# Schematic_Kpad.net
KiCad netlist of a schematic drawn in Altium Designer
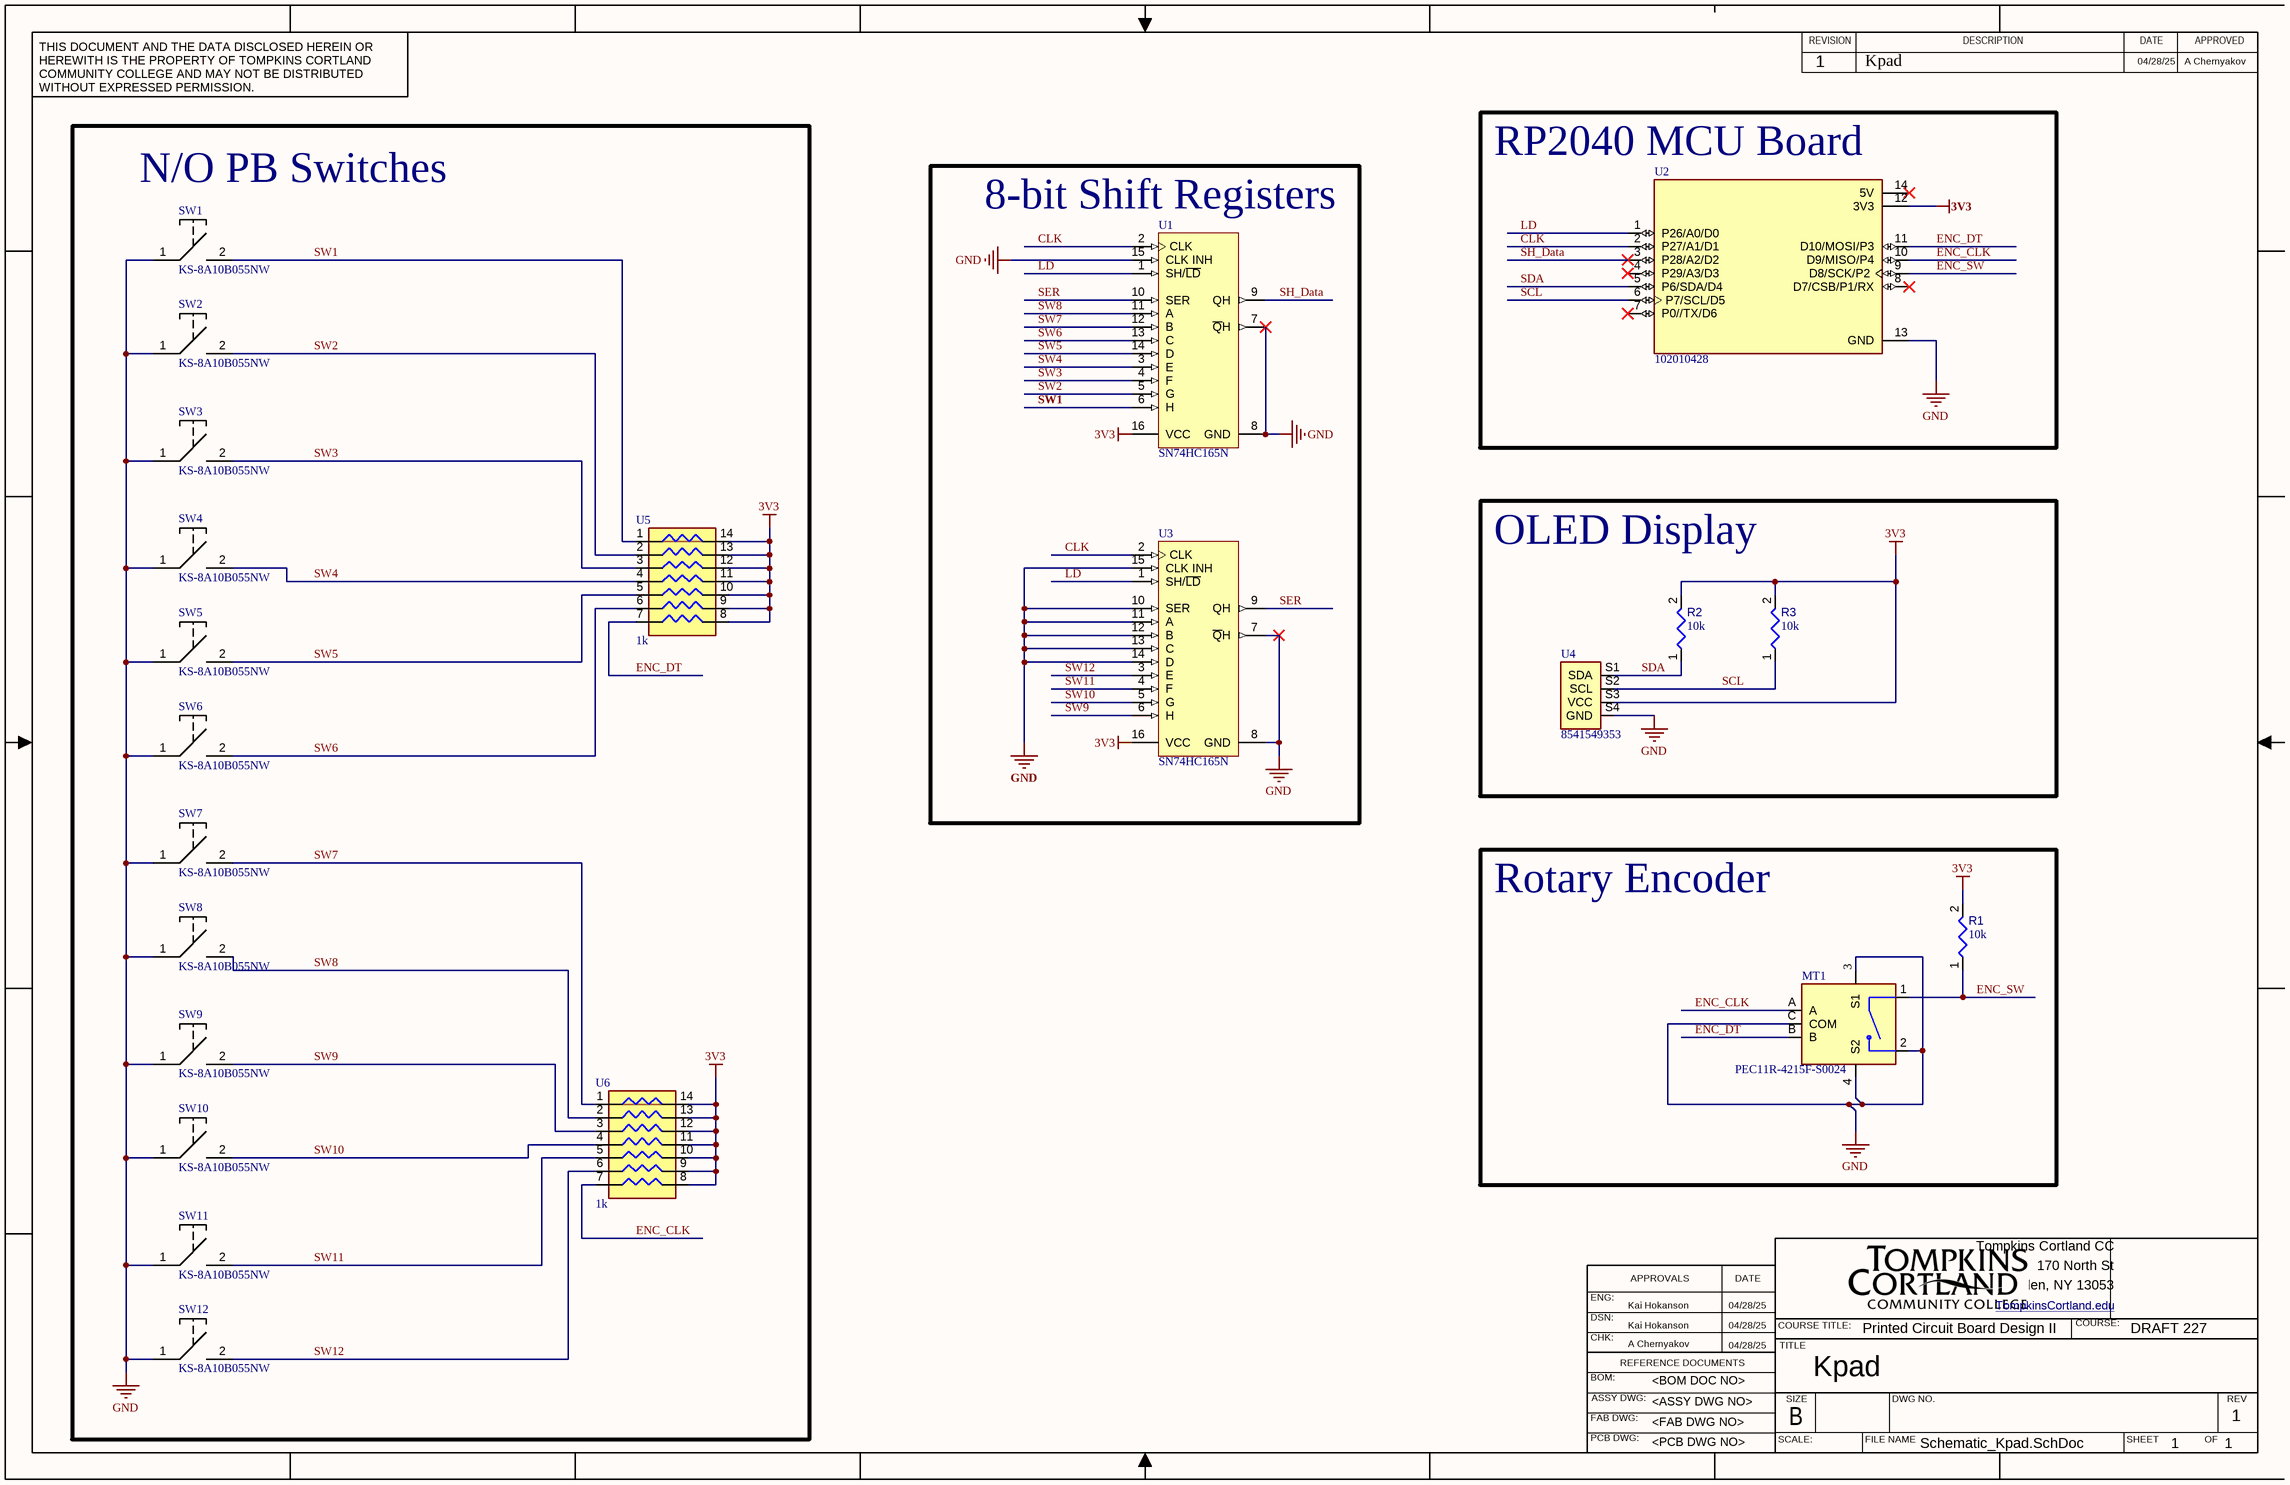
[diagram p0: Schematic_Kpad.SchDoc]

(export (version "E")
  (design (tool "Eeschema 10.0.6"))
  (components
    (comp (ref "MT1")
      (value "PEC11R-4215F-S0024")
      (footprint "FP-PEC11R-4215F-S0024-MFG")
      (description "Incremental Encoder, 12 Mm, Contact Rating 10 Ma - 5 Vdc")
      (libsource (lib "Tompkins Cortland Community College") (part "PEC11R-4215F-S0024"))
    )
    (comp (ref "R1")
      (value "10k")
      (footprint "RESA60-630X240")
      (description "Axial Resistor, 10 KOhm, +/- 1%, 0.25 W, -55 to 155 degC, 2-Pin THD, RoHS, Bulk")
      (fields (field (name "TOLERANCE") "1%") (field (name "POWER") "250mW"))
      (libsource (lib "Tompkins Cortland Community College") (part "RES-2"))
    )
    (comp (ref "R2")
      (value "10k")
      (footprint "RESA60-630X240")
      (description "Axial Resistor, 10 KOhm, +/- 1%, 0.25 W, -55 to 155 degC, 2-Pin THD, RoHS, Bulk")
      (fields (field (name "TOLERANCE") "1%") (field (name "POWER") "250mW"))
      (libsource (lib "Tompkins Cortland Community College") (part "RES-2"))
    )
    (comp (ref "R3")
      (value "10k")
      (footprint "RESA60-630X240")
      (description "Axial Resistor, 10 KOhm, +/- 1%, 0.25 W, -55 to 155 degC, 2-Pin THD, RoHS, Bulk")
      (fields (field (name "TOLERANCE") "1%") (field (name "POWER") "250mW"))
      (libsource (lib "Tompkins Cortland Community College") (part "RES-2"))
    )
    (comp (ref "SW1")
      (value "KS-8A10B055NW")
      (footprint "KS-8A10B055NW-Footprint-1")
      (description "SPST momentary switch 15.40mmx15.40mm")
      (libsource (lib "Tompkins Cortland Community College") (part "KS-8A10B055NW-Symbol-1"))
    )
    (comp (ref "SW2")
      (value "KS-8A10B055NW")
      (footprint "KS-8A10B055NW-Footprint-1")
      (description "SPST momentary switch 15.40mmx15.40mm")
      (libsource (lib "Tompkins Cortland Community College") (part "KS-8A10B055NW-Symbol-1"))
    )
    (comp (ref "SW3")
      (value "KS-8A10B055NW")
      (footprint "KS-8A10B055NW-Footprint-1")
      (description "SPST momentary switch 15.40mmx15.40mm")
      (libsource (lib "Tompkins Cortland Community College") (part "KS-8A10B055NW-Symbol-1"))
    )
    (comp (ref "SW4")
      (value "KS-8A10B055NW")
      (footprint "KS-8A10B055NW-Footprint-1")
      (description "SPST momentary switch 15.40mmx15.40mm")
      (libsource (lib "Tompkins Cortland Community College") (part "KS-8A10B055NW-Symbol-1"))
    )
    (comp (ref "SW5")
      (value "KS-8A10B055NW")
      (footprint "KS-8A10B055NW-Footprint-1")
      (description "SPST momentary switch 15.40mmx15.40mm")
      (libsource (lib "Tompkins Cortland Community College") (part "KS-8A10B055NW-Symbol-1"))
    )
    (comp (ref "SW6")
      (value "KS-8A10B055NW")
      (footprint "KS-8A10B055NW-Footprint-1")
      (description "SPST momentary switch 15.40mmx15.40mm")
      (libsource (lib "Tompkins Cortland Community College") (part "KS-8A10B055NW-Symbol-1"))
    )
    (comp (ref "SW7")
      (value "KS-8A10B055NW")
      (footprint "KS-8A10B055NW-Footprint-1")
      (description "SPST momentary switch 15.40mmx15.40mm")
      (libsource (lib "Tompkins Cortland Community College") (part "KS-8A10B055NW-Symbol-1"))
    )
    (comp (ref "SW8")
      (value "KS-8A10B055NW")
      (footprint "KS-8A10B055NW-Footprint-1")
      (description "SPST momentary switch 15.40mmx15.40mm")
      (libsource (lib "Tompkins Cortland Community College") (part "KS-8A10B055NW-Symbol-1"))
    )
    (comp (ref "SW9")
      (value "KS-8A10B055NW")
      (footprint "KS-8A10B055NW-Footprint-1")
      (description "SPST momentary switch 15.40mmx15.40mm")
      (libsource (lib "Tompkins Cortland Community College") (part "KS-8A10B055NW-Symbol-1"))
    )
    (comp (ref "SW10")
      (value "KS-8A10B055NW")
      (footprint "KS-8A10B055NW-Footprint-1")
      (description "SPST momentary switch 15.40mmx15.40mm")
      (libsource (lib "Tompkins Cortland Community College") (part "KS-8A10B055NW-Symbol-1"))
    )
    (comp (ref "SW11")
      (value "KS-8A10B055NW")
      (footprint "KS-8A10B055NW-Footprint-1")
      (description "SPST momentary switch 15.40mmx15.40mm")
      (libsource (lib "Tompkins Cortland Community College") (part "KS-8A10B055NW-Symbol-1"))
    )
    (comp (ref "SW12")
      (value "KS-8A10B055NW")
      (footprint "KS-8A10B055NW-Footprint-1")
      (description "SPST momentary switch 15.40mmx15.40mm")
      (libsource (lib "Tompkins Cortland Community College") (part "KS-8A10B055NW-Symbol-1"))
    )
    (comp (ref "U1")
      (value "SN74HC165N")
      (footprint "TI-N0016A")
      (libsource (lib "Tompkins Cortland Community College") (part "TI-SNX4XXX165X-16"))
    )
    (comp (ref "U2")
      (value "102010428")
      (footprint "MODULE_102010428")
      (description "RP2040 XIAO RP2040 series ARMÂ® CortexÂ®-M0+ MCU 32-Bit Embedded Evaluation Board")
      (libsource (lib "Tompkins Cortland Community College") (part "102010428"))
    )
    (comp (ref "U3")
      (value "SN74HC165N")
      (footprint "TI-N0016A")
      (libsource (lib "Tompkins Cortland Community College") (part "TI-SNX4XXX165X-16"))
    )
    (comp (ref "U4")
      (value "8541549353")
      (footprint "New footprint 1")
      (description "MakerFocus 2pcs I2C OLED Display Module 0.91 Inch")
      (libsource (lib "Tompkins Cortland Community College") (part "8541549353"))
    )
    (comp (ref "U5")
      (value "1k")
      (footprint "DIP794W45P254L1969H508Q14")
      (description "RES ARRAY 7 RES 1K OHM 14DIP")
      (fields (field (name "TOLERANCE") "2%") (field (name "POWER") "250mW"))
      (libsource (lib "Tompkins Cortland Community College") (part "4114R-1-331LF"))
    )
    (comp (ref "U6")
      (value "1k")
      (footprint "DIP794W45P254L1969H508Q14")
      (description "RES ARRAY 7 RES 1K OHM 14DIP")
      (fields (field (name "TOLERANCE") "2%") (field (name "POWER") "250mW"))
      (libsource (lib "Tompkins Cortland Community College") (part "4114R-1-331LF"))
    )
  )
  (nets
    (net (code "1") (name "/CLK") (class "Default")
      (node (ref "U1") (pin "2") (pinfunction "CLK_2") (pintype "input"))
      (node (ref "U2") (pin "2") (pinfunction "P27/A1/D1_2") (pintype "bidirectional"))
      (node (ref "U3") (pin "2") (pinfunction "CLK_2") (pintype "input"))
    )
    (net (code "2") (name "/ENC_CLK") (class "Default")
      (node (ref "MT1") (pin "A") (pinfunction "A_A") (pintype "passive"))
      (node (ref "U2") (pin "10") (pinfunction "D9/MISO/P4_10") (pintype "bidirectional"))
      (node (ref "U6") (pin "7") (pinfunction "7_7") (pintype "passive"))
    )
    (net (code "3") (name "/ENC_DT") (class "Default")
      (node (ref "MT1") (pin "B") (pinfunction "B_B") (pintype "passive"))
      (node (ref "U2") (pin "11") (pinfunction "D10/MOSI/P3_11") (pintype "bidirectional"))
      (node (ref "U5") (pin "7") (pinfunction "7_7") (pintype "passive"))
    )
    (net (code "4") (name "/ENC_SW") (class "Default")
      (node (ref "MT1") (pin "1") (pinfunction "1_1") (pintype "passive"))
      (node (ref "R1") (pin "1") (pinfunction "1_1") (pintype "passive"))
      (node (ref "U2") (pin "9") (pinfunction "D8/SCK/P2_9") (pintype "bidirectional"))
    )
    (net (code "5") (name "/LD") (class "Default")
      (node (ref "U1") (pin "1") (pinfunction "SH/~{LD}_1") (pintype "input"))
      (node (ref "U2") (pin "1") (pinfunction "P26/A0/D0_1") (pintype "bidirectional"))
      (node (ref "U3") (pin "1") (pinfunction "SH/~{LD}_1") (pintype "input"))
    )
    (net (code "6") (name "/SCL") (class "Default")
      (node (ref "R3") (pin "1") (pinfunction "1_1") (pintype "passive"))
      (node (ref "U2") (pin "6") (pinfunction "P7/SCL/D5_6") (pintype "bidirectional"))
      (node (ref "U4") (pin "S2") (pinfunction "SCL_S2") (pintype "passive"))
    )
    (net (code "7") (name "/SDA") (class "Default")
      (node (ref "R2") (pin "1") (pinfunction "1_1") (pintype "passive"))
      (node (ref "U2") (pin "5") (pinfunction "P6/SDA/D4_5") (pintype "bidirectional"))
      (node (ref "U4") (pin "S1") (pinfunction "SDA_S1") (pintype "passive"))
    )
    (net (code "8") (name "/SER") (class "Default")
      (node (ref "U1") (pin "10") (pinfunction "SER_10") (pintype "input"))
      (node (ref "U3") (pin "9") (pinfunction "QH_9") (pintype "output"))
    )
    (net (code "9") (name "/SH_Data") (class "Default")
      (node (ref "U1") (pin "9") (pinfunction "QH_9") (pintype "output"))
      (node (ref "U2") (pin "3") (pinfunction "P28/A2/D2_3") (pintype "bidirectional"))
    )
    (net (code "10") (name "/SW1") (class "Default")
      (node (ref "SW1") (pin "2") (pinfunction "2_2") (pintype "passive"))
      (node (ref "U1") (pin "6") (pinfunction "H_6") (pintype "input"))
      (node (ref "U5") (pin "1") (pinfunction "1_1") (pintype "passive"))
    )
    (net (code "11") (name "/SW2") (class "Default")
      (node (ref "SW2") (pin "2") (pinfunction "2_2") (pintype "passive"))
      (node (ref "U1") (pin "5") (pinfunction "G_5") (pintype "input"))
      (node (ref "U5") (pin "2") (pinfunction "2_2") (pintype "passive"))
    )
    (net (code "12") (name "/SW3") (class "Default")
      (node (ref "SW3") (pin "2") (pinfunction "2_2") (pintype "passive"))
      (node (ref "U1") (pin "4") (pinfunction "F_4") (pintype "input"))
      (node (ref "U5") (pin "3") (pinfunction "3_3") (pintype "passive"))
    )
    (net (code "13") (name "/SW4") (class "Default")
      (node (ref "SW4") (pin "2") (pinfunction "2_2") (pintype "passive"))
      (node (ref "U1") (pin "3") (pinfunction "E_3") (pintype "input"))
      (node (ref "U5") (pin "4") (pinfunction "4_4") (pintype "passive"))
    )
    (net (code "14") (name "/SW5") (class "Default")
      (node (ref "SW5") (pin "2") (pinfunction "2_2") (pintype "passive"))
      (node (ref "U1") (pin "14") (pinfunction "D_14") (pintype "input"))
      (node (ref "U5") (pin "5") (pinfunction "5_5") (pintype "passive"))
    )
    (net (code "15") (name "/SW6") (class "Default")
      (node (ref "SW6") (pin "2") (pinfunction "2_2") (pintype "passive"))
      (node (ref "U1") (pin "13") (pinfunction "C_13") (pintype "input"))
      (node (ref "U5") (pin "6") (pinfunction "6_6") (pintype "passive"))
    )
    (net (code "16") (name "/SW7") (class "Default")
      (node (ref "SW7") (pin "2") (pinfunction "2_2") (pintype "passive"))
      (node (ref "U1") (pin "12") (pinfunction "B_12") (pintype "input"))
      (node (ref "U6") (pin "1") (pinfunction "1_1") (pintype "passive"))
    )
    (net (code "17") (name "/SW8") (class "Default")
      (node (ref "SW8") (pin "2") (pinfunction "2_2") (pintype "passive"))
      (node (ref "U1") (pin "11") (pinfunction "A_11") (pintype "input"))
      (node (ref "U6") (pin "2") (pinfunction "2_2") (pintype "passive"))
    )
    (net (code "18") (name "/SW9") (class "Default")
      (node (ref "SW9") (pin "2") (pinfunction "2_2") (pintype "passive"))
      (node (ref "U3") (pin "6") (pinfunction "H_6") (pintype "input"))
      (node (ref "U6") (pin "3") (pinfunction "3_3") (pintype "passive"))
    )
    (net (code "19") (name "/SW10") (class "Default")
      (node (ref "SW10") (pin "2") (pinfunction "2_2") (pintype "passive"))
      (node (ref "U3") (pin "5") (pinfunction "G_5") (pintype "input"))
      (node (ref "U6") (pin "4") (pinfunction "4_4") (pintype "passive"))
    )
    (net (code "20") (name "/SW11") (class "Default")
      (node (ref "SW11") (pin "2") (pinfunction "2_2") (pintype "passive"))
      (node (ref "U3") (pin "4") (pinfunction "F_4") (pintype "input"))
      (node (ref "U6") (pin "5") (pinfunction "5_5") (pintype "passive"))
    )
    (net (code "21") (name "/SW12") (class "Default")
      (node (ref "SW12") (pin "2") (pinfunction "2_2") (pintype "passive"))
      (node (ref "U3") (pin "3") (pinfunction "E_3") (pintype "input"))
      (node (ref "U6") (pin "6") (pinfunction "6_6") (pintype "passive"))
    )
    (net (code "22") (name "3V3") (class "Default")
      (node (ref "R1") (pin "2") (pinfunction "2_2") (pintype "passive"))
      (node (ref "R2") (pin "2") (pinfunction "2_2") (pintype "passive"))
      (node (ref "R3") (pin "2") (pinfunction "2_2") (pintype "passive"))
      (node (ref "U1") (pin "16") (pinfunction "VCC_16") (pintype "power_in"))
      (node (ref "U2") (pin "12") (pinfunction "3V3_12") (pintype "power_in"))
      (node (ref "U3") (pin "16") (pinfunction "VCC_16") (pintype "power_in"))
      (node (ref "U4") (pin "S3") (pinfunction "VCC_S3") (pintype "power_in"))
      (node (ref "U5") (pin "10") (pinfunction "10_10") (pintype "passive"))
      (node (ref "U5") (pin "11") (pinfunction "11_11") (pintype "passive"))
      (node (ref "U5") (pin "12") (pinfunction "12_12") (pintype "passive"))
      (node (ref "U5") (pin "13") (pinfunction "13_13") (pintype "passive"))
      (node (ref "U5") (pin "14") (pinfunction "14_14") (pintype "passive"))
      (node (ref "U5") (pin "8") (pinfunction "8_8") (pintype "passive"))
      (node (ref "U5") (pin "9") (pinfunction "9_9") (pintype "passive"))
      (node (ref "U6") (pin "10") (pinfunction "10_10") (pintype "passive"))
      (node (ref "U6") (pin "11") (pinfunction "11_11") (pintype "passive"))
      (node (ref "U6") (pin "12") (pinfunction "12_12") (pintype "passive"))
      (node (ref "U6") (pin "13") (pinfunction "13_13") (pintype "passive"))
      (node (ref "U6") (pin "14") (pinfunction "14_14") (pintype "passive"))
      (node (ref "U6") (pin "8") (pinfunction "8_8") (pintype "passive"))
      (node (ref "U6") (pin "9") (pinfunction "9_9") (pintype "passive"))
    )
    (net (code "23") (name "GND") (class "Default")
      (node (ref "MT1") (pin "2") (pinfunction "2_2") (pintype "passive"))
      (node (ref "MT1") (pin "3") (pinfunction "S1_3") (pintype "passive"))
      (node (ref "MT1") (pin "4") (pinfunction "S2_4") (pintype "passive"))
      (node (ref "MT1") (pin "C") (pinfunction "COM_C") (pintype "passive"))
      (node (ref "SW1") (pin "1") (pinfunction "1_1") (pintype "passive"))
      (node (ref "SW10") (pin "1") (pinfunction "1_1") (pintype "passive"))
      (node (ref "SW11") (pin "1") (pinfunction "1_1") (pintype "passive"))
      (node (ref "SW12") (pin "1") (pinfunction "1_1") (pintype "passive"))
      (node (ref "SW2") (pin "1") (pinfunction "1_1") (pintype "passive"))
      (node (ref "SW3") (pin "1") (pinfunction "1_1") (pintype "passive"))
      (node (ref "SW4") (pin "1") (pinfunction "1_1") (pintype "passive"))
      (node (ref "SW5") (pin "1") (pinfunction "1_1") (pintype "passive"))
      (node (ref "SW6") (pin "1") (pinfunction "1_1") (pintype "passive"))
      (node (ref "SW7") (pin "1") (pinfunction "1_1") (pintype "passive"))
      (node (ref "SW8") (pin "1") (pinfunction "1_1") (pintype "passive"))
      (node (ref "SW9") (pin "1") (pinfunction "1_1") (pintype "passive"))
      (node (ref "U1") (pin "15") (pinfunction "CLK_INH_15") (pintype "input"))
      (node (ref "U1") (pin "7") (pinfunction "~{Q}H_7") (pintype "output"))
      (node (ref "U1") (pin "8") (pinfunction "GND_8") (pintype "power_in"))
      (node (ref "U2") (pin "13") (pinfunction "GND_13") (pintype "power_in"))
      (node (ref "U3") (pin "10") (pinfunction "SER_10") (pintype "input"))
      (node (ref "U3") (pin "11") (pinfunction "A_11") (pintype "input"))
      (node (ref "U3") (pin "12") (pinfunction "B_12") (pintype "input"))
      (node (ref "U3") (pin "13") (pinfunction "C_13") (pintype "input"))
      (node (ref "U3") (pin "14") (pinfunction "D_14") (pintype "input"))
      (node (ref "U3") (pin "15") (pinfunction "CLK_INH_15") (pintype "input"))
      (node (ref "U3") (pin "7") (pinfunction "~{Q}H_7") (pintype "output"))
      (node (ref "U3") (pin "8") (pinfunction "GND_8") (pintype "power_in"))
      (node (ref "U4") (pin "S4") (pinfunction "GND_S4") (pintype "power_in"))
    )
    (net (code "24") (name "unconnected-(U2-5V-Pad14)") (class "Default")
      (node (ref "U2") (pin "14") (pinfunction "5V_14") (pintype "power_in+no_connect"))
    )
    (net (code "25") (name "unconnected-(U2-D7{slash}CSB{slash}P1{slash}RX-Pad8)") (class "Default")
      (node (ref "U2") (pin "8") (pinfunction "D7/CSB/P1/RX_8") (pintype "bidirectional+no_connect"))
    )
    (net (code "26") (name "unconnected-(U2-P0{slash}{slash}TX{slash}D6-Pad7)") (class "Default")
      (node (ref "U2") (pin "7") (pinfunction "P0//TX/D6_7") (pintype "bidirectional+no_connect"))
    )
    (net (code "27") (name "unconnected-(U2-P29{slash}A3{slash}D3-Pad4)") (class "Default")
      (node (ref "U2") (pin "4") (pinfunction "P29/A3/D3_4") (pintype "bidirectional+no_connect"))
    )
  )
)
